# untitled.net
KiCad netlist of a schematic drawn in EAGLE
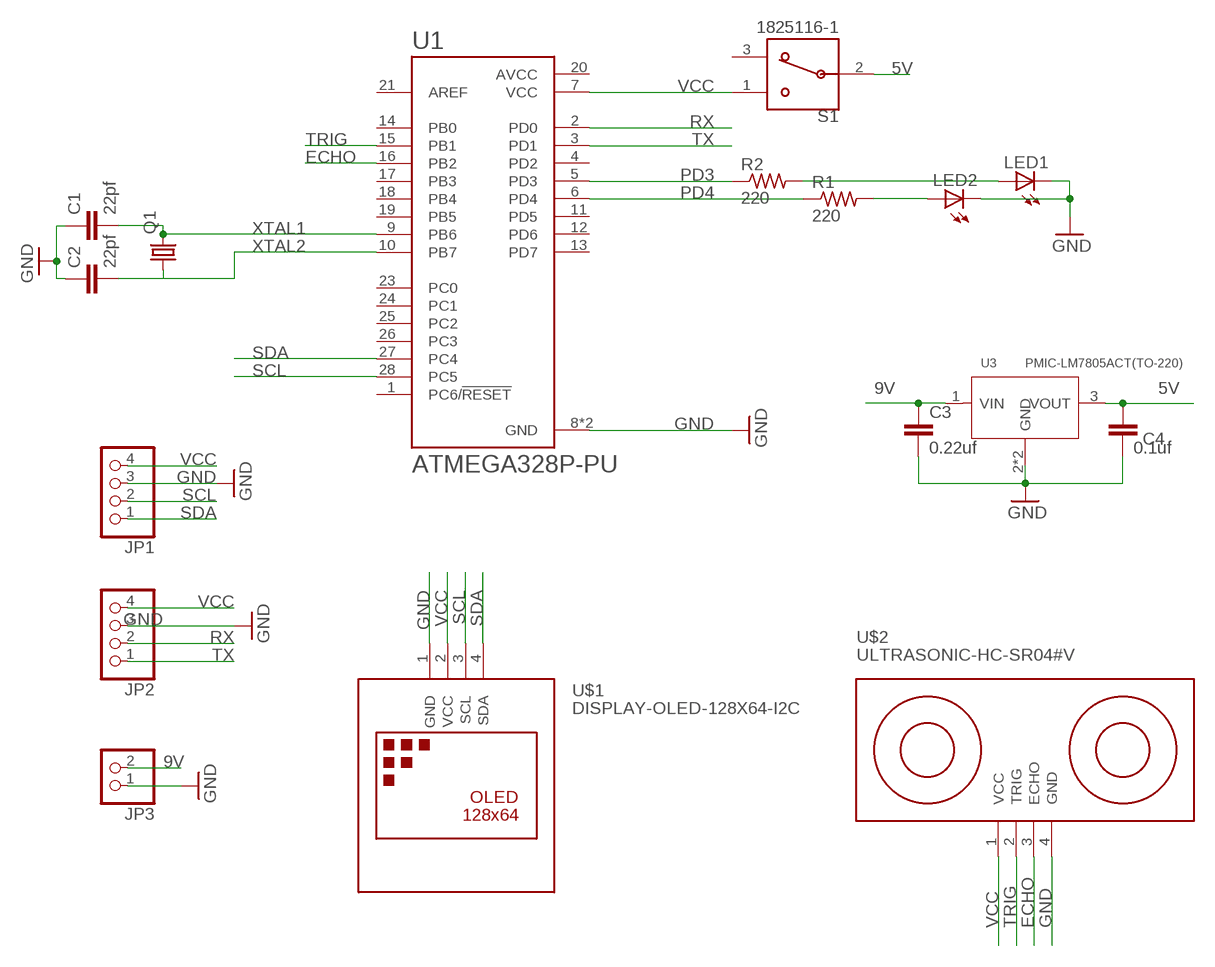
[diagram p0: schematic, sheet 1]

(export (version "E")
  (design (tool "Eeschema 10.0.6"))
  (components
    (comp (ref "C1")
      (value "22pf")
      (footprint "eagle-import:C2.5-2")
      (libsource (lib "eagle-import") (part "C2.5/2"))
    )
    (comp (ref "C2")
      (value "22pf")
      (footprint "eagle-import:C2.5-2")
      (libsource (lib "eagle-import") (part "C2.5/2"))
    )
    (comp (ref "C3")
      (value "0.22uf")
      (footprint "eagle-import:C2.5-2")
      (libsource (lib "eagle-import") (part "C2.5/2"))
    )
    (comp (ref "C4")
      (value "0.1uf")
      (footprint "eagle-import:C2.5-2")
      (libsource (lib "eagle-import") (part "C2.5/2"))
    )
    (comp (ref "JP1")
      (value "HEADER-1X4")
      (footprint "eagle-import:1X04_OVAL")
      (libsource (lib "eagle-import") (part "HEADER-1X4"))
    )
    (comp (ref "JP2")
      (value "HEADER-1X4")
      (footprint "eagle-import:1X04_OVAL")
      (libsource (lib "eagle-import") (part "HEADER-1X4"))
    )
    (comp (ref "JP3")
      (value "HEADER-1X2")
      (footprint "eagle-import:1X02_OVAL")
      (libsource (lib "eagle-import") (part "HEADER-1X2"))
    )
    (comp (ref "LED1")
      (value "LED3MM")
      (footprint "eagle-import:LED3MM")
      (libsource (lib "eagle-import") (part "LED3MM"))
    )
    (comp (ref "LED2")
      (value "LED3MM")
      (footprint "eagle-import:LED3MM")
      (libsource (lib "eagle-import") (part "LED3MM"))
    )
    (comp (ref "Q1")
      (value "CRYSTALHC49S")
      (footprint "eagle-import:HC49_S")
      (libsource (lib "eagle-import") (part "CRYSTALHC49S"))
    )
    (comp (ref "R1")
      (value "220")
      (footprint "eagle-import:0204_5")
      (libsource (lib "eagle-import") (part "R-US_0204/5"))
    )
    (comp (ref "R2")
      (value "220")
      (footprint "eagle-import:0204_5")
      (libsource (lib "eagle-import") (part "R-US_0204/5"))
    )
    (comp (ref "S1")
      (value "1825116-1")
      (footprint "eagle-import:SW_1825116-1")
      (fields (field (name "MF") "TE Connectivity"))
      (libsource (lib "eagle-import") (part "1825116-1"))
    )
    (comp (ref "U$1")
      (value "DISPLAY-OLED-128X64-I2C")
      (footprint "eagle-import:DISPLAY-OLED-128X64-I2C")
      (libsource (lib "eagle-import") (part "DISPLAY-OLED-128X64-I2C"))
    )
    (comp (ref "U$2")
      (value "ULTRASONIC-HC-SR04#V")
      (footprint "eagle-import:ULTRASONIC-HC-SR04#V")
      (libsource (lib "eagle-import") (part "ULTRASONIC-HC-SR04#V"))
    )
    (comp (ref "U1")
      (value "ATMEGA328P-PU")
      (footprint "eagle-import:DIP794W46P254L2967H457Q28B")
      (fields (field (name "MF") "Microchip Technology"))
      (libsource (lib "eagle-import") (part "ATMEGA328P-PU"))
    )
    (comp (ref "U3")
      (value "PMIC-LM7805ACT(TO-220)")
      (footprint "eagle-import:TO-220")
      (fields (field (name "MF") "ON Semiconductor") (field (name "MP") "LM7805ACT"))
      (libsource (lib "eagle-import") (part "PMIC-LM7805ACT(TO-220)"))
    )
  )
  (nets
    (net (code "1") (name "/5V") (class "Default")
      (node (ref "C4") (pin "1") (pinfunction "1_1") (pintype "passive"))
      (node (ref "S1") (pin "2") (pinfunction "2_2") (pintype "passive"))
      (node (ref "U3") (pin "3") (pinfunction "VOUT_3") (pintype "bidirectional"))
    )
    (net (code "2") (name "/9V") (class "Default")
      (node (ref "C3") (pin "1") (pinfunction "1_1") (pintype "passive"))
      (node (ref "JP3") (pin "2") (pinfunction "2_2") (pintype "passive"))
      (node (ref "U3") (pin "1") (pinfunction "VIN_1") (pintype "bidirectional"))
    )
    (net (code "3") (name "/AVCC") (class "Default")
      (node (ref "U1") (pin "20") (pinfunction "AVCC_20") (pintype "power_in"))
    )
    (net (code "4") (name "/ECHO") (class "Default")
      (node (ref "U$2") (pin "3") (pinfunction "ECHO_3") (pintype "output"))
      (node (ref "U1") (pin "16") (pinfunction "PB2_16") (pintype "bidirectional"))
    )
    (net (code "5") (name "/PD3") (class "Default")
      (node (ref "R2") (pin "1") (pinfunction "1_1") (pintype "passive"))
      (node (ref "U1") (pin "5") (pinfunction "PD3_5") (pintype "bidirectional"))
    )
    (net (code "6") (name "/PD4") (class "Default")
      (node (ref "R1") (pin "1") (pinfunction "1_1") (pintype "passive"))
      (node (ref "U1") (pin "6") (pinfunction "PD4_6") (pintype "bidirectional"))
    )
    (net (code "7") (name "/RX") (class "Default")
      (node (ref "JP2") (pin "2") (pinfunction "2_2") (pintype "passive"))
      (node (ref "U1") (pin "2") (pinfunction "PD0_2") (pintype "bidirectional"))
    )
    (net (code "8") (name "/SCL") (class "Default")
      (node (ref "JP1") (pin "2") (pinfunction "2_2") (pintype "passive"))
      (node (ref "U$1") (pin "3") (pinfunction "SCL_3") (pintype "bidirectional"))
      (node (ref "U1") (pin "28") (pinfunction "PC5_28") (pintype "bidirectional"))
    )
    (net (code "9") (name "/SDA") (class "Default")
      (node (ref "JP1") (pin "1") (pinfunction "1_1") (pintype "passive"))
      (node (ref "U$1") (pin "4") (pinfunction "SDA_4") (pintype "bidirectional"))
      (node (ref "U1") (pin "27") (pinfunction "PC4_27") (pintype "bidirectional"))
    )
    (net (code "10") (name "/TRIG") (class "Default")
      (node (ref "U$2") (pin "2") (pinfunction "TRIG_2") (pintype "input"))
      (node (ref "U1") (pin "15") (pinfunction "PB1_15") (pintype "bidirectional"))
    )
    (net (code "11") (name "/TX") (class "Default")
      (node (ref "JP2") (pin "1") (pinfunction "1_1") (pintype "passive"))
      (node (ref "U1") (pin "3") (pinfunction "PD1_3") (pintype "bidirectional"))
    )
    (net (code "12") (name "/VCC") (class "Default")
      (node (ref "JP1") (pin "4") (pinfunction "4_4") (pintype "passive"))
      (node (ref "JP2") (pin "4") (pinfunction "4_4") (pintype "passive"))
      (node (ref "S1") (pin "1") (pinfunction "1_1") (pintype "passive"))
      (node (ref "U$1") (pin "2") (pinfunction "VCC_2") (pintype "power_in"))
      (node (ref "U$2") (pin "1") (pinfunction "VCC_1") (pintype "power_in"))
      (node (ref "U1") (pin "7") (pinfunction "VCC_7") (pintype "power_in"))
    )
    (net (code "13") (name "/XTAL1") (class "Default")
      (node (ref "C1") (pin "2") (pinfunction "2_2") (pintype "passive"))
      (node (ref "Q1") (pin "2") (pinfunction "2_2") (pintype "passive"))
      (node (ref "U1") (pin "9") (pinfunction "PB6_9") (pintype "bidirectional"))
    )
    (net (code "14") (name "/XTAL2") (class "Default")
      (node (ref "C2") (pin "2") (pinfunction "2_2") (pintype "passive"))
      (node (ref "Q1") (pin "1") (pinfunction "1_1") (pintype "passive"))
      (node (ref "U1") (pin "10") (pinfunction "PB7_10") (pintype "bidirectional"))
    )
    (net (code "15") (name "GND") (class "Default")
      (node (ref "C1") (pin "1") (pinfunction "1_1") (pintype "passive"))
      (node (ref "C2") (pin "1") (pinfunction "1_1") (pintype "passive"))
      (node (ref "C3") (pin "2") (pinfunction "2_2") (pintype "passive"))
      (node (ref "C4") (pin "2") (pinfunction "2_2") (pintype "passive"))
      (node (ref "JP1") (pin "3") (pinfunction "3_3") (pintype "passive"))
      (node (ref "JP2") (pin "3") (pinfunction "3_3") (pintype "passive"))
      (node (ref "JP3") (pin "1") (pinfunction "1_1") (pintype "passive"))
      (node (ref "LED1") (pin "K") (pinfunction "C_K") (pintype "passive"))
      (node (ref "LED2") (pin "K") (pinfunction "C_K") (pintype "passive"))
      (node (ref "U$1") (pin "1") (pinfunction "GND_1") (pintype "power_in"))
      (node (ref "U$2") (pin "4") (pinfunction "GND_4") (pintype "power_in"))
      (node (ref "U1") (pin "22") (pinfunction "GND_22") (pintype "power_in"))
      (node (ref "U1") (pin "8") (pinfunction "GND_8") (pintype "power_in"))
      (node (ref "U3") (pin "2") (pinfunction "GND_2") (pintype "bidirectional"))
      (node (ref "U3") (pin "HEAT") (pinfunction "GND_HEAT") (pintype "bidirectional"))
    )
    (net (code "16") (name "Net-(LED1-PadA)") (class "Default")
      (node (ref "LED1") (pin "A") (pinfunction "A_A") (pintype "passive"))
      (node (ref "R2") (pin "2") (pinfunction "2_2") (pintype "passive"))
    )
    (net (code "17") (name "Net-(LED2-PadA)") (class "Default")
      (node (ref "LED2") (pin "A") (pinfunction "A_A") (pintype "passive"))
      (node (ref "R1") (pin "2") (pinfunction "2_2") (pintype "passive"))
    )
    (net (code "18") (name "unconnected-(S1-Pad3)") (class "Default")
      (node (ref "S1") (pin "3") (pinfunction "3_3") (pintype "passive"))
    )
    (net (code "19") (name "unconnected-(U1-AREF-Pad21)") (class "Default")
      (node (ref "U1") (pin "21") (pinfunction "AREF_21") (pintype "input"))
    )
    (net (code "20") (name "unconnected-(U1-PB0-Pad14)") (class "Default")
      (node (ref "U1") (pin "14") (pinfunction "PB0_14") (pintype "bidirectional"))
    )
    (net (code "21") (name "unconnected-(U1-PB3-Pad17)") (class "Default")
      (node (ref "U1") (pin "17") (pinfunction "PB3_17") (pintype "bidirectional"))
    )
    (net (code "22") (name "unconnected-(U1-PB4-Pad18)") (class "Default")
      (node (ref "U1") (pin "18") (pinfunction "PB4_18") (pintype "bidirectional"))
    )
    (net (code "23") (name "unconnected-(U1-PB5-Pad19)") (class "Default")
      (node (ref "U1") (pin "19") (pinfunction "PB5_19") (pintype "bidirectional"))
    )
    (net (code "24") (name "unconnected-(U1-PC0-Pad23)") (class "Default")
      (node (ref "U1") (pin "23") (pinfunction "PC0_23") (pintype "bidirectional"))
    )
    (net (code "25") (name "unconnected-(U1-PC1-Pad24)") (class "Default")
      (node (ref "U1") (pin "24") (pinfunction "PC1_24") (pintype "bidirectional"))
    )
    (net (code "26") (name "unconnected-(U1-PC2-Pad25)") (class "Default")
      (node (ref "U1") (pin "25") (pinfunction "PC2_25") (pintype "bidirectional"))
    )
    (net (code "27") (name "unconnected-(U1-PC3-Pad26)") (class "Default")
      (node (ref "U1") (pin "26") (pinfunction "PC3_26") (pintype "bidirectional"))
    )
    (net (code "28") (name "unconnected-(U1-PC6{slash}~{RESET}-Pad1)") (class "Default")
      (node (ref "U1") (pin "1") (pinfunction "PC6/~{RESET}_1") (pintype "bidirectional"))
    )
    (net (code "29") (name "unconnected-(U1-PD2-Pad4)") (class "Default")
      (node (ref "U1") (pin "4") (pinfunction "PD2_4") (pintype "bidirectional"))
    )
    (net (code "30") (name "unconnected-(U1-PD5-Pad11)") (class "Default")
      (node (ref "U1") (pin "11") (pinfunction "PD5_11") (pintype "bidirectional"))
    )
    (net (code "31") (name "unconnected-(U1-PD6-Pad12)") (class "Default")
      (node (ref "U1") (pin "12") (pinfunction "PD6_12") (pintype "bidirectional"))
    )
    (net (code "32") (name "unconnected-(U1-PD7-Pad13)") (class "Default")
      (node (ref "U1") (pin "13") (pinfunction "PD7_13") (pintype "bidirectional"))
    )
  )
)
